# MicroController.net
KiCad netlist of a schematic drawn in Altium Designer
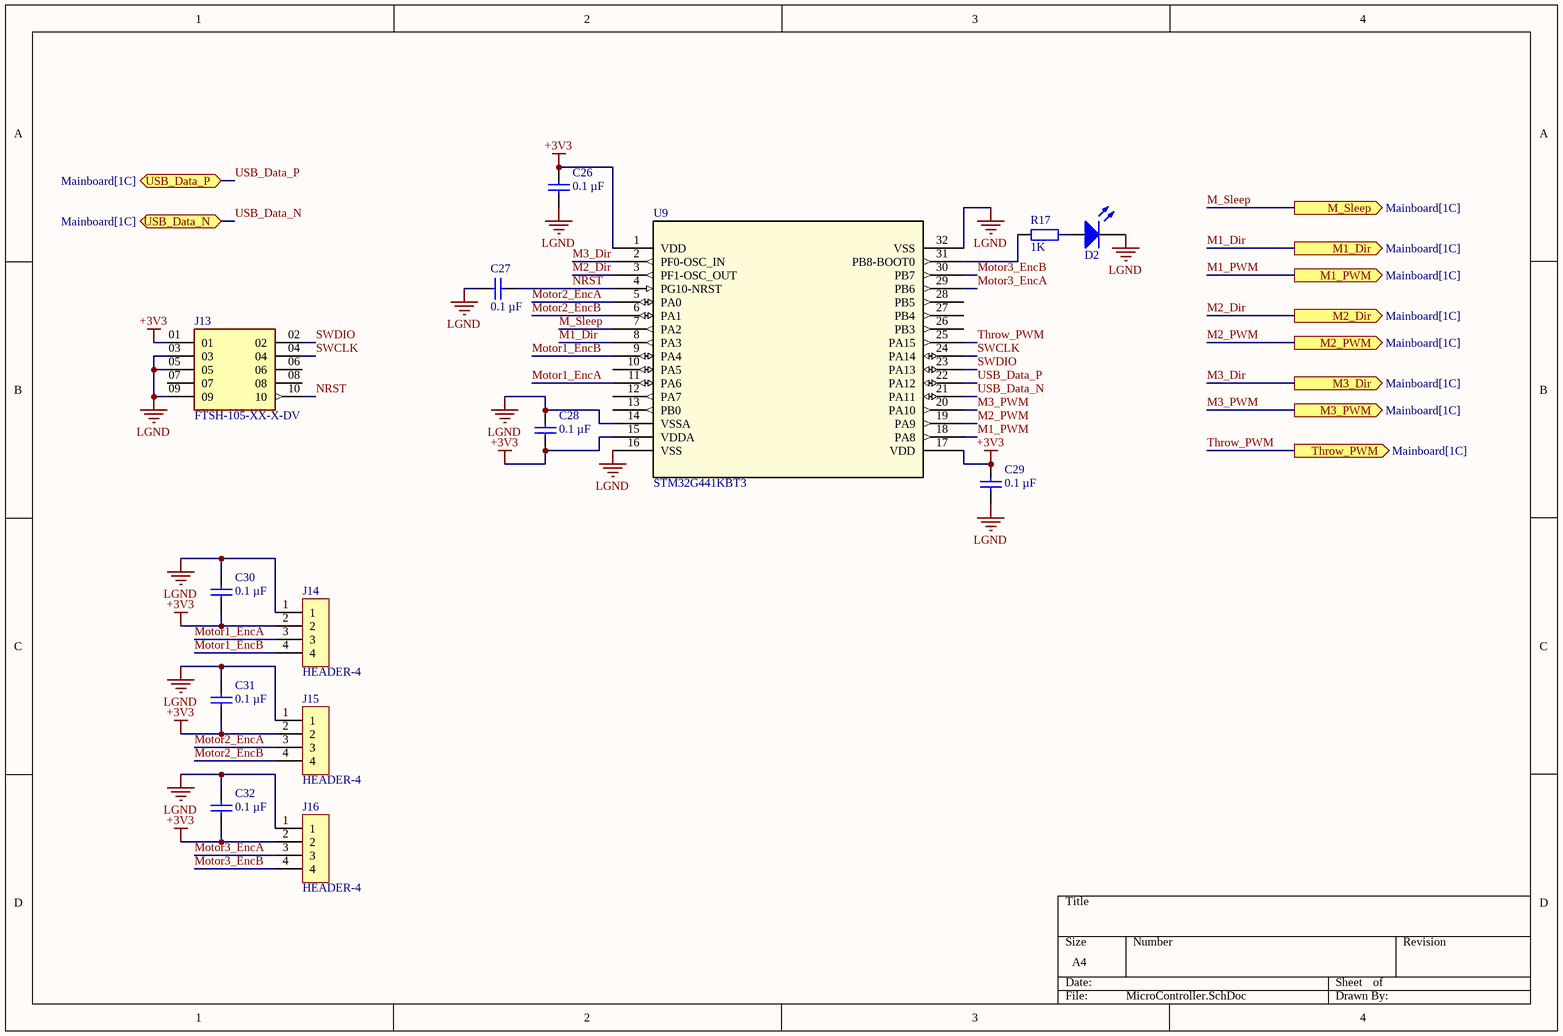
[diagram p0: MicroController.SchDoc]

(export (version "E")
  (design (tool "Eeschema 10.0.6"))
  (components
    (comp (ref "C26")
      (value "0.1 µF")
      (footprint "CAP_0603")
      (description "Multilayer Ceramic Capacitors")
      (fields (field (name "TOLERANCE") "10%") (field (name "Comment") "MLCC"))
      (libsource (lib "Tartu University") (part "MLCC"))
    )
    (comp (ref "C27")
      (value "0.1 µF")
      (footprint "CAP_0603")
      (description "Multilayer Ceramic Capacitors")
      (fields (field (name "TOLERANCE") "10%") (field (name "Comment") "MLCC"))
      (libsource (lib "Tartu University") (part "MLCC"))
    )
    (comp (ref "C28")
      (value "0.1 µF")
      (footprint "CAP_0603")
      (description "Multilayer Ceramic Capacitors")
      (fields (field (name "TOLERANCE") "10%") (field (name "Comment") "MLCC"))
      (libsource (lib "Tartu University") (part "MLCC"))
    )
    (comp (ref "C29")
      (value "0.1 µF")
      (footprint "CAP_0603")
      (description "Multilayer Ceramic Capacitors")
      (fields (field (name "TOLERANCE") "10%") (field (name "Comment") "MLCC"))
      (libsource (lib "Tartu University") (part "MLCC"))
    )
    (comp (ref "C30")
      (value "0.1 µF")
      (footprint "CAP_0603")
      (description "Multilayer Ceramic Capacitors")
      (fields (field (name "TOLERANCE") "10%") (field (name "Comment") "MLCC"))
      (libsource (lib "Tartu University") (part "MLCC"))
    )
    (comp (ref "C31")
      (value "0.1 µF")
      (footprint "CAP_0603")
      (description "Multilayer Ceramic Capacitors")
      (fields (field (name "TOLERANCE") "10%") (field (name "Comment") "MLCC"))
      (libsource (lib "Tartu University") (part "MLCC"))
    )
    (comp (ref "C32")
      (value "0.1 µF")
      (footprint "CAP_0603")
      (description "Multilayer Ceramic Capacitors")
      (fields (field (name "TOLERANCE") "10%") (field (name "Comment") "MLCC"))
      (libsource (lib "Tartu University") (part "MLCC"))
    )
    (comp (ref "D2")
      (value "LED")
      (footprint "0603_GREEN")
      (description "LED Emitters")
      (libsource (lib "Tartu University") (part "LED"))
    )
    (comp (ref "J13")
      (value "FTSH-105-XX-X-DV")
      (footprint "SAMTEC_FTSH-105-XX-X-DV")
      (description "Connector Header Surface Mount 10 position 0.050\" (1.27mm)")
      (libsource (lib "Tartu University") (part "FTSH-105-XX-X-DV"))
    )
    (comp (ref "J14")
      (value "HEADER-4")
      (footprint "MICRO-MATCH-FOB-04")
      (fields (field (name "SOURCE") "connectors_micromatch.SchLib"))
      (libsource (lib "Tartu University") (part "HEADER-4"))
    )
    (comp (ref "J15")
      (value "HEADER-4")
      (footprint "MICRO-MATCH-FOB-04")
      (fields (field (name "SOURCE") "connectors_micromatch.SchLib"))
      (libsource (lib "Tartu University") (part "HEADER-4"))
    )
    (comp (ref "J16")
      (value "HEADER-4")
      (footprint "MICRO-MATCH-FOB-04")
      (fields (field (name "SOURCE") "connectors_micromatch.SchLib"))
      (libsource (lib "Tartu University") (part "HEADER-4"))
    )
    (comp (ref "R17")
      (value "1K")
      (footprint "RC0603N")
      (description "Chip Resistors")
      (fields (field (name "Comment") "RES"))
      (libsource (lib "Tartu University") (part "MELF"))
    )
    (comp (ref "U9")
      (value "STM32G441KBT3")
      (footprint "LQFP32_7X7_STM")
      (description "No Description Available")
      (fields (field (name "COPYRIGHT") "Copyright (C) 2022 Ultra Librarian. All rights reserved."))
      (libsource (lib "STM32G441KBT3") (part "STM32G441KBT3"))
    )
  )
  (nets
    (net (code "1") (name "+3V3") (class "Default")
      (node (ref "C26") (pin "2") (pinfunction "2_2") (pintype "passive"))
      (node (ref "C28") (pin "1") (pinfunction "1_1") (pintype "passive"))
      (node (ref "C29") (pin "2") (pinfunction "2_2") (pintype "passive"))
      (node (ref "C30") (pin "1") (pinfunction "1_1") (pintype "passive"))
      (node (ref "C31") (pin "1") (pinfunction "1_1") (pintype "passive"))
      (node (ref "C32") (pin "1") (pinfunction "1_1") (pintype "passive"))
      (node (ref "J13") (pin "01") (pinfunction "01_01") (pintype "passive"))
      (node (ref "J14") (pin "2") (pinfunction "2_2") (pintype "passive"))
      (node (ref "J15") (pin "2") (pinfunction "2_2") (pintype "passive"))
      (node (ref "J16") (pin "2") (pinfunction "2_2") (pintype "passive"))
      (node (ref "U9") (pin "1") (pinfunction "VDD_1") (pintype "power_in"))
      (node (ref "U9") (pin "15") (pinfunction "VDDA_15") (pintype "power_in"))
      (node (ref "U9") (pin "17") (pinfunction "VDD_17") (pintype "power_in"))
    )
    (net (code "2") (name "/M1_Dir") (class "Default")
      (node (ref "U9") (pin "8") (pinfunction "PA3_8") (pintype "output"))
    )
    (net (code "3") (name "/M1_PWM") (class "Default")
      (node (ref "U9") (pin "18") (pinfunction "PA8_18") (pintype "output"))
    )
    (net (code "4") (name "/M2_Dir") (class "Default")
      (node (ref "U9") (pin "3") (pinfunction "PF1-OSC_OUT_3") (pintype "output"))
    )
    (net (code "5") (name "/M2_PWM") (class "Default")
      (node (ref "U9") (pin "19") (pinfunction "PA9_19") (pintype "output"))
    )
    (net (code "6") (name "/M3_Dir") (class "Default")
      (node (ref "U9") (pin "2") (pinfunction "PF0-OSC_IN_2") (pintype "output"))
    )
    (net (code "7") (name "/M3_PWM") (class "Default")
      (node (ref "U9") (pin "20") (pinfunction "PA10_20") (pintype "output"))
    )
    (net (code "8") (name "/M_Sleep") (class "Default")
      (node (ref "U9") (pin "7") (pinfunction "PA2_7") (pintype "output"))
    )
    (net (code "9") (name "/Motor1_EncA") (class "Default")
      (node (ref "J14") (pin "3") (pinfunction "3_3") (pintype "passive"))
      (node (ref "U9") (pin "11") (pinfunction "PA6_11") (pintype "bidirectional"))
    )
    (net (code "10") (name "/Motor1_EncB") (class "Default")
      (node (ref "J14") (pin "4") (pinfunction "4_4") (pintype "passive"))
      (node (ref "U9") (pin "9") (pinfunction "PA4_9") (pintype "bidirectional"))
    )
    (net (code "11") (name "/Motor2_EncA") (class "Default")
      (node (ref "J15") (pin "3") (pinfunction "3_3") (pintype "passive"))
      (node (ref "U9") (pin "5") (pinfunction "PA0_5") (pintype "bidirectional"))
    )
    (net (code "12") (name "/Motor2_EncB") (class "Default")
      (node (ref "J15") (pin "4") (pinfunction "4_4") (pintype "passive"))
      (node (ref "U9") (pin "6") (pinfunction "PA1_6") (pintype "bidirectional"))
    )
    (net (code "13") (name "/Motor3_EncA") (class "Default")
      (node (ref "J16") (pin "3") (pinfunction "3_3") (pintype "passive"))
      (node (ref "U9") (pin "29") (pinfunction "PB6_29") (pintype "output"))
    )
    (net (code "14") (name "/Motor3_EncB") (class "Default")
      (node (ref "J16") (pin "4") (pinfunction "4_4") (pintype "passive"))
      (node (ref "U9") (pin "30") (pinfunction "PB7_30") (pintype "output"))
    )
    (net (code "15") (name "/NRST") (class "Default")
      (node (ref "C27") (pin "1") (pinfunction "1_1") (pintype "passive"))
      (node (ref "J13") (pin "10") (pinfunction "10_10") (pintype "output"))
      (node (ref "U9") (pin "4") (pinfunction "PG10-NRST_4") (pintype "input"))
    )
    (net (code "16") (name "/SWCLK") (class "Default")
      (node (ref "J13") (pin "04") (pinfunction "04_04") (pintype "passive"))
      (node (ref "U9") (pin "24") (pinfunction "PA14_24") (pintype "bidirectional"))
    )
    (net (code "17") (name "/SWDIO") (class "Default")
      (node (ref "J13") (pin "02") (pinfunction "02_02") (pintype "passive"))
      (node (ref "U9") (pin "23") (pinfunction "PA13_23") (pintype "bidirectional"))
    )
    (net (code "18") (name "/Throw_PWM") (class "Default")
      (node (ref "U9") (pin "25") (pinfunction "PA15_25") (pintype "output"))
    )
    (net (code "19") (name "/USB_Data_N") (class "Default")
      (node (ref "U9") (pin "21") (pinfunction "PA11_21") (pintype "bidirectional"))
    )
    (net (code "20") (name "/USB_Data_P") (class "Default")
      (node (ref "U9") (pin "22") (pinfunction "PA12_22") (pintype "bidirectional"))
    )
    (net (code "21") (name "LGND") (class "Default")
      (node (ref "C26") (pin "1") (pinfunction "1_1") (pintype "passive"))
      (node (ref "C27") (pin "2") (pinfunction "2_2") (pintype "passive"))
      (node (ref "C28") (pin "2") (pinfunction "2_2") (pintype "passive"))
      (node (ref "C29") (pin "1") (pinfunction "1_1") (pintype "passive"))
      (node (ref "C30") (pin "2") (pinfunction "2_2") (pintype "passive"))
      (node (ref "C31") (pin "2") (pinfunction "2_2") (pintype "passive"))
      (node (ref "C32") (pin "2") (pinfunction "2_2") (pintype "passive"))
      (node (ref "D2") (pin "2") (pinfunction "K_2") (pintype "passive"))
      (node (ref "J13") (pin "03") (pinfunction "03_03") (pintype "passive"))
      (node (ref "J13") (pin "05") (pinfunction "05_05") (pintype "passive"))
      (node (ref "J13") (pin "09") (pinfunction "09_09") (pintype "passive"))
      (node (ref "J14") (pin "1") (pinfunction "1_1") (pintype "passive"))
      (node (ref "J15") (pin "1") (pinfunction "1_1") (pintype "passive"))
      (node (ref "J16") (pin "1") (pinfunction "1_1") (pintype "passive"))
      (node (ref "U9") (pin "14") (pinfunction "VSSA_14") (pintype "passive"))
      (node (ref "U9") (pin "16") (pinfunction "VSS_16") (pintype "passive"))
      (node (ref "U9") (pin "32") (pinfunction "VSS_32") (pintype "passive"))
    )
    (net (code "22") (name "Net-(D2-A)") (class "Default")
      (node (ref "D2") (pin "1") (pinfunction "A_1") (pintype "passive"))
      (node (ref "R17") (pin "1") (pinfunction "1_1") (pintype "passive"))
    )
    (net (code "23") (name "Net-(U9-PB8-BOOT0)") (class "Default")
      (node (ref "R17") (pin "2") (pinfunction "2_2") (pintype "passive"))
      (node (ref "U9") (pin "31") (pinfunction "PB8-BOOT0_31") (pintype "output"))
    )
    (net (code "24") (name "unconnected-(J13-Pad06)") (class "Default")
      (node (ref "J13") (pin "06") (pinfunction "06_06") (pintype "passive"))
    )
    (net (code "25") (name "unconnected-(J13-Pad07)") (class "Default")
      (node (ref "J13") (pin "07") (pinfunction "07_07") (pintype "passive"))
    )
    (net (code "26") (name "unconnected-(J13-Pad08)") (class "Default")
      (node (ref "J13") (pin "08") (pinfunction "08_08") (pintype "passive"))
    )
    (net (code "27") (name "unconnected-(U9-PA5-Pad10)") (class "Default")
      (node (ref "U9") (pin "10") (pinfunction "PA5_10") (pintype "bidirectional"))
    )
    (net (code "28") (name "unconnected-(U9-PA7-Pad12)") (class "Default")
      (node (ref "U9") (pin "12") (pinfunction "PA7_12") (pintype "output"))
    )
    (net (code "29") (name "unconnected-(U9-PB0-Pad13)") (class "Default")
      (node (ref "U9") (pin "13") (pinfunction "PB0_13") (pintype "output"))
    )
    (net (code "30") (name "unconnected-(U9-PB3-Pad26)") (class "Default")
      (node (ref "U9") (pin "26") (pinfunction "PB3_26") (pintype "output"))
    )
    (net (code "31") (name "unconnected-(U9-PB4-Pad27)") (class "Default")
      (node (ref "U9") (pin "27") (pinfunction "PB4_27") (pintype "output"))
    )
    (net (code "32") (name "unconnected-(U9-PB5-Pad28)") (class "Default")
      (node (ref "U9") (pin "28") (pinfunction "PB5_28") (pintype "output"))
    )
  )
)
